# Unknown_WaterSensor.net
KiCad netlist of a schematic drawn in Altium Designer
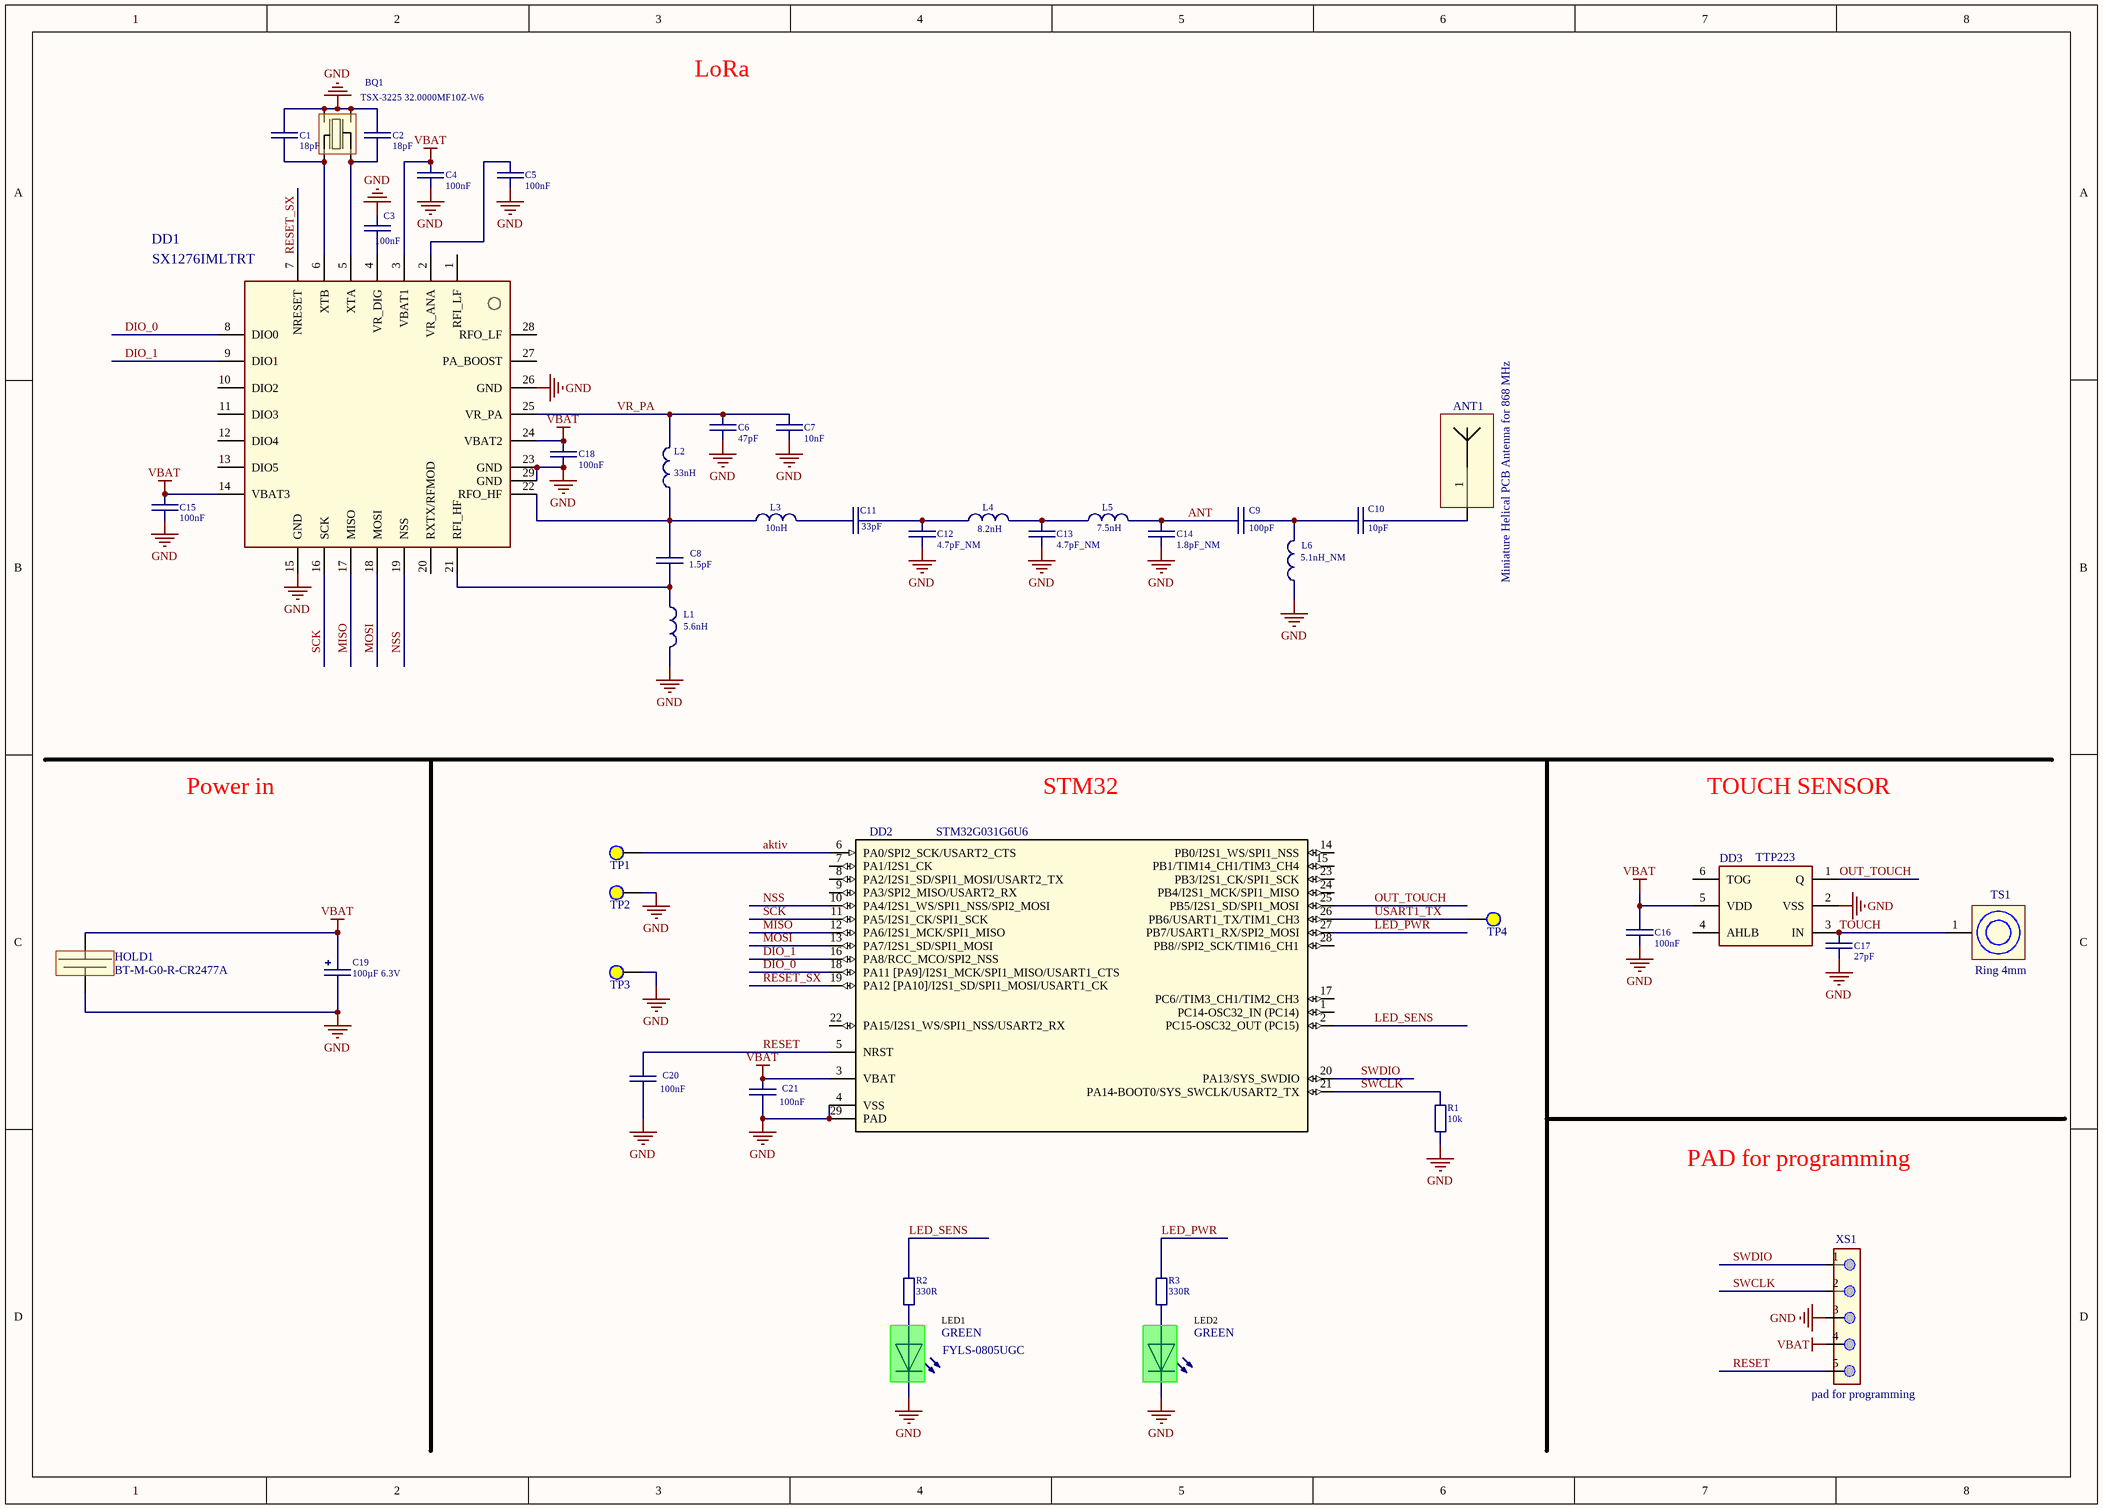
[diagram p0: Unknown WaterSensor.SCHDOC]

(export (version "E")
  (design (tool "Eeschema 10.0.6"))
  (components
    (comp (ref "ANT1")
      (value "Miniature Helical PCB Antenna for 868 MHz")
      (footprint "ANTENNA868_915MHZ_A2N")
      (libsource (lib "*") (part "Miniature Helical PCB Antenna for 868 MHz"))
    )
    (comp (ref "BQ1")
      (value "TSX-3225 32.0000MF10Z-W6")
      (footprint "3225")
      (description "32MHz ±10ppm Crystal 12pF 40 Ohms 4-SMD (3.20mm x 2.50mm)")
      (libsource (lib "CRYSTALS") (part "TSX-3225 32.0000MF10Z-W6"))
    )
    (comp (ref "C1")
      (value "C0402, 18pF, C0G")
      (footprint "C0402")
      (fields (field (name "CAPACITANCE") "18pF"))
      (libsource (lib "CAPACITORS") (part "C0402, 18pF, C0G"))
    )
    (comp (ref "C2")
      (value "C0402, 18pF, C0G")
      (footprint "C0402")
      (fields (field (name "CAPACITANCE") "18pF"))
      (libsource (lib "CAPACITORS") (part "C0402, 18pF, C0G"))
    )
    (comp (ref "C3")
      (value "C0402, 100nF,  16V, X7R")
      (footprint "C0402")
      (fields
        (field (name "MANUFACTURER") "MURATA")
        (field (name "MANUFACTURER PART NUMBER") "GRM155R71C104KA88D")
        (field (name "CAPACITANCE") "100nF")
      )
      (libsource (lib "CAPACITORS") (part "C0402, 100nF,  16V, X7R"))
    )
    (comp (ref "C4")
      (value "C0402, 100nF,  16V, X7R")
      (footprint "C0402")
      (fields
        (field (name "MANUFACTURER") "MURATA")
        (field (name "MANUFACTURER PART NUMBER") "GRM155R71C104KA88D")
        (field (name "CAPACITANCE") "100nF")
      )
      (libsource (lib "CAPACITORS") (part "C0402, 100nF,  16V, X7R"))
    )
    (comp (ref "C5")
      (value "C0402, 100nF,  16V, X7R")
      (footprint "C0402")
      (fields
        (field (name "MANUFACTURER") "MURATA")
        (field (name "MANUFACTURER PART NUMBER") "GRM155R71C104KA88D")
        (field (name "CAPACITANCE") "100nF")
      )
      (libsource (lib "CAPACITORS") (part "C0402, 100nF,  16V, X7R"))
    )
    (comp (ref "C6")
      (value "C0402, 47pF, C0G")
      (footprint "C0402")
      (fields (field (name "CAPACITANCE") "47pF"))
      (libsource (lib "*") (part "C0402, 47pF, C0G"))
    )
    (comp (ref "C7")
      (value "C0402, 10nF, X7R")
      (footprint "C0402")
      (fields (field (name "CAPACITANCE") "10nF"))
      (libsource (lib "*") (part "C0402, 10nF, X7R"))
    )
    (comp (ref "C8")
      (value "C0402, 1.5pF, C0G")
      (footprint "C0402")
      (fields (field (name "CAPACITANCE") "1.5pF"))
      (libsource (lib "CAPACITORS") (part "C0402, 1.5pF, C0G"))
    )
    (comp (ref "C9")
      (value "C0402, 100pF,  50V")
      (footprint "C0402")
      (fields (field (name "CAPACITANCE") "100pF"))
      (libsource (lib "CAPACITORS") (part "C0402, 100pF,  50V"))
    )
    (comp (ref "C10")
      (value "C0402, 10pF,  50V")
      (footprint "C0402")
      (fields (field (name "CAPACITANCE") "10pF"))
      (libsource (lib "CAPACITORS") (part "C0402, 10pF,  50V"))
    )
    (comp (ref "C11")
      (value "C0402, 33pF, C0G")
      (footprint "C0402")
      (fields (field (name "CAPACITANCE") "33pF"))
      (libsource (lib "*") (part "C0402, 33pF, C0G"))
    )
    (comp (ref "C12")
      (value "C0402, 4.7pF, C0G_NOT_MOUNT")
      (footprint "C0402")
      (fields (field (name "CAPACITANCE") "4.7pF_NM"))
      (libsource (lib "*") (part "C0402, 4.7pF, C0G"))
    )
    (comp (ref "C13")
      (value "C0402, 4.7pF, C0G_NOT_MOUNT")
      (footprint "C0402")
      (fields (field (name "CAPACITANCE") "4.7pF_NM"))
      (libsource (lib "*") (part "C0402, 4.7pF, C0G"))
    )
    (comp (ref "C14")
      (value "C0402, 1.8pF, C0G_NOT_MOUNT")
      (footprint "C0402")
      (fields (field (name "CAPACITANCE") "1.8pF_NM"))
      (libsource (lib "*") (part "C0402, 1.8pF, C0G"))
    )
    (comp (ref "C15")
      (value "C0402, 100nF,  16V, X7R")
      (footprint "C0402")
      (fields
        (field (name "MANUFACTURER") "MURATA")
        (field (name "MANUFACTURER PART NUMBER") "GRM155R71C104KA88D")
        (field (name "CAPACITANCE") "100nF")
      )
      (libsource (lib "CAPACITORS") (part "C0402, 100nF,  16V, X7R"))
    )
    (comp (ref "C16")
      (value "C0402, 100nF,  16V, X7R")
      (footprint "C0402")
      (fields
        (field (name "MANUFACTURER") "MURATA")
        (field (name "MANUFACTURER PART NUMBER") "GRM155R71C104KA88D")
        (field (name "CAPACITANCE") "100nF")
      )
      (libsource (lib "CAPACITORS") (part "C0402, 100nF,  16V, X7R"))
    )
    (comp (ref "C17")
      (value "C0402, 27pF, C0G")
      (footprint "C0402")
      (fields (field (name "CAPACITANCE") "27pF"))
      (libsource (lib "CAPACITORS") (part "C0402, 27pF, C0G"))
    )
    (comp (ref "C18")
      (value "C0402, 100nF,  16V, X7R")
      (footprint "C0402")
      (fields
        (field (name "MANUFACTURER") "MURATA")
        (field (name "MANUFACTURER PART NUMBER") "GRM155R71C104KA88D")
        (field (name "CAPACITANCE") "100nF")
      )
      (libsource (lib "CAPACITORS") (part "C0402, 100nF,  16V, X7R"))
    )
    (comp (ref "C19")
      (value "865080142007")
      (footprint "WCAP-ASLI_5x5.5")
      (description "Aluminium Electrolytic Capacitors - SMD WCAP-ASLI 100uF 6.3V 20% SMD/SMT")
      (fields (field (name "ALTIUM_UNNAMED_1") "100µF 6.3V"))
      (libsource (lib "*") (part "865080142007"))
    )
    (comp (ref "C20")
      (value "C0402, 100nF,  16V, X7R")
      (footprint "C0402")
      (fields
        (field (name "MANUFACTURER") "MURATA")
        (field (name "MANUFACTURER PART NUMBER") "GRM155R71C104KA88D")
        (field (name "CAPACITANCE") "100nF")
      )
      (libsource (lib "CAPACITORS") (part "C0402, 100nF,  16V, X7R"))
    )
    (comp (ref "C21")
      (value "C0402, 100nF,  16V, X7R")
      (footprint "C0402")
      (fields
        (field (name "MANUFACTURER") "MURATA")
        (field (name "MANUFACTURER PART NUMBER") "GRM155R71C104KA88D")
        (field (name "CAPACITANCE") "100nF")
      )
      (libsource (lib "CAPACITORS") (part "C0402, 100nF,  16V, X7R"))
    )
    (comp (ref "DD1")
      (value "SX1276IMLTRT")
      (footprint "vqfn28_6x6mm")
      (description "SX1276 - Low Power Integrated UHF Transceiver with loRa Modem")
      (libsource (lib "DIGITAL and ANALOG ICs") (part "SX1276IMLTRT"))
    )
    (comp (ref "DD2")
      (value "STM32G031G6U6")
      (footprint "UFQFPN-28")
      (description "ARM® Cortex®-M0+ STM32G0 Microcontroller IC 32-Bit 64MHz 32KB (32K x 8) FLASH 28-UFQFPN (4x4)")
      (libsource (lib "SparkFun") (part "STM32G031G6U6"))
    )
    (comp (ref "DD3")
      (value "TTP223")
      (footprint "SOT23-6")
      (description "1 KEY TOUCH PAD DETECTOR IC")
      (libsource (lib "DIGITAL and ANALOG ICs") (part "TTP223"))
    )
    (comp (ref "HOLD1")
      (value "BT-M-G0-R-CR2477A")
      (footprint "SMTU2477N-LF")
      (description "Coin Cell Battery Holders FOR CR2477N, SMD")
      (libsource (lib "CONNECTORS") (part "SMTU2477N-LF"))
    )
    (comp (ref "L1")
      (value "LQG15HS5N6C02D")
      (footprint "L0402")
      (description "L0402, 5.6nH")
      (fields (field (name "ALTIUM_UNNAMED_1") "5.6nH"))
      (libsource (lib "INDUCTORS") (part "LQG15HS5N6C02D"))
    )
    (comp (ref "L2")
      (value "LQW15AN33NJ00D")
      (footprint "L0402")
      (description "L0402, 33nH")
      (fields (field (name "ALTIUM_UNNAMED_1") "33nH"))
      (libsource (lib "INDUCTORS") (part "LQW15AN33NJ00D"))
    )
    (comp (ref "L3")
      (value "LQG15HS10NJ02D")
      (footprint "L0402")
      (description "L0402, 10nH")
      (fields (field (name "ALTIUM_UNNAMED_1") "10nH"))
      (libsource (lib "*") (part "LQG15HS10NJ02D"))
    )
    (comp (ref "L4")
      (value "LQG15HS8N2J02D")
      (footprint "L0402")
      (description "L0402, 8.2nH")
      (fields (field (name "ALTIUM_UNNAMED_1") "8.2nH"))
      (libsource (lib "*") (part "LQG15HS8N2J02D"))
    )
    (comp (ref "L5")
      (value "LQG15HS7N5J02D")
      (footprint "L0402")
      (description "L0402, 7.5nH")
      (fields (field (name "ALTIUM_UNNAMED_1") "7.5nH"))
      (libsource (lib "*") (part "LQG15HS7N5J02D"))
    )
    (comp (ref "L6")
      (value "LQG15HN5N1S02D_NOT_MOUNT")
      (footprint "L0402")
      (description "L0402, 5.1nH_NOT_MOUNT")
      (fields (field (name "ALTIUM_UNNAMED_1") "5.1nH_NM"))
      (libsource (lib "*") (part "LQG15HN5N1S02D"))
    )
    (comp (ref "LED1")
      (value "FYLS-0805UGC")
      (footprint "LED_0805_G")
      (description "LED, GREEN, 0805")
      (fields (field (name "ALTIUM_UNNAMED_1") "GREEN"))
      (libsource (lib "LED") (part "FYLS-0805UGC"))
    )
    (comp (ref "LED2")
      (value "FYLS-0805UGC")
      (footprint "LED_0805_G")
      (description "LED, GREEN, 0805")
      (fields (field (name "ALTIUM_UNNAMED_1") "GREEN"))
      (libsource (lib "LED") (part "FYLS-0805UGC"))
    )
    (comp (ref "R1")
      (value "R0402, 10k 1%")
      (footprint "R0402")
      (fields (field (name "PART NUMBER") "RC0402JR-0710KL_YAGEO") (field (name "RESISTANCE") "10k"))
      (libsource (lib "RESISTOR") (part "R0402, 10k 1%"))
    )
    (comp (ref "R2")
      (value "R0402, 330R 5%")
      (footprint "R0402")
      (fields
        (field (name "RESISTANCE") "330R")
        (field (name "MANUFACTURER") "Panasonic Electronic Components")
        (field (name "TOLERANCE") "5 %")
        (field (name "MANUFACTURER PART NUMBER") "ERJ-2GEJ331X")
      )
      (libsource (lib "RESISTOR") (part "R0402, 330R 5%"))
    )
    (comp (ref "R3")
      (value "R0402, 330R 5%")
      (footprint "R0402")
      (fields
        (field (name "RESISTANCE") "330R")
        (field (name "MANUFACTURER") "Panasonic Electronic Components")
        (field (name "TOLERANCE") "5 %")
        (field (name "MANUFACTURER PART NUMBER") "ERJ-2GEJ331X")
      )
      (libsource (lib "RESISTOR") (part "R0402, 330R 5%"))
    )
    (comp (ref "TP1")
      (value "Test Point 1mm pad")
      (footprint "Test Point 1mm")
      (libsource (lib "CONNECTORS") (part "Test Point 1mm pad"))
    )
    (comp (ref "TP2")
      (value "Test Point 1mm pad")
      (footprint "Test Point 1mm")
      (libsource (lib "CONNECTORS") (part "Test Point 1mm pad"))
    )
    (comp (ref "TP3")
      (value "Test Point 1mm pad")
      (footprint "Test Point 1mm")
      (libsource (lib "CONNECTORS") (part "Test Point 1mm pad"))
    )
    (comp (ref "TP4")
      (value "Test Point 1mm pad")
      (footprint "Test Point 1mm")
      (libsource (lib "CONNECTORS") (part "Test Point 1mm pad"))
    )
    (comp (ref "TS1")
      (value "Ring 4mm")
      (footprint "Ring 4mm")
      (description "touch spring 13x8.5mm")
      (libsource (lib "*") (part "Ring 4mm"))
    )
    (comp (ref "XS1")
      (value "pad for programming")
      (footprint "pad for programming 5x2mm")
      (description "pad for programming 5x2mm")
      (libsource (lib "*") (part "pad for programming 5x2mm"))
    )
  )
  (nets
    (net (code "1") (name "/ANT") (class "Default")
      (node (ref "C14") (pin "2") (pintype "passive"))
      (node (ref "C9") (pin "1") (pintype "passive"))
      (node (ref "L5") (pin "2") (pinfunction "2_2") (pintype "passive"))
    )
    (net (code "2") (name "/DIO_0") (class "Default")
      (node (ref "DD1") (pin "8") (pinfunction "DIO0_8") (pintype "passive"))
      (node (ref "DD2") (pin "18") (pinfunction "PA11_[PA9]/I2S1_MCK/SPI1_MISO/USART1_CTS_18") (pintype "bidirectional"))
    )
    (net (code "3") (name "/DIO_1") (class "Default")
      (node (ref "DD1") (pin "9") (pinfunction "DIO1_9") (pintype "passive"))
      (node (ref "DD2") (pin "16") (pinfunction "PA8/RCC_MCO/SPI2_NSS_16") (pintype "bidirectional"))
    )
    (net (code "4") (name "/LED_PWR") (class "Default")
      (node (ref "DD2") (pin "27") (pinfunction "PB7/USART1_RX/SPI2_MOSI_27") (pintype "bidirectional"))
      (node (ref "R3") (pin "2") (pintype "passive"))
    )
    (net (code "5") (name "/LED_SENS") (class "Default")
      (node (ref "DD2") (pin "2") (pinfunction "PC15-OSC32_OUT_(PC15)_2") (pintype "bidirectional"))
      (node (ref "R2") (pin "2") (pintype "passive"))
    )
    (net (code "6") (name "/MISO") (class "Default")
      (node (ref "DD1") (pin "17") (pinfunction "MISO_17") (pintype "passive"))
      (node (ref "DD2") (pin "12") (pinfunction "PA6/I2S1_MCK/SPI1_MISO_12") (pintype "bidirectional"))
    )
    (net (code "7") (name "/MOSI") (class "Default")
      (node (ref "DD1") (pin "18") (pinfunction "MOSI_18") (pintype "passive"))
      (node (ref "DD2") (pin "13") (pinfunction "PA7/I2S1_SD/SPI1_MOSI_13") (pintype "bidirectional"))
    )
    (net (code "8") (name "/NSS") (class "Default")
      (node (ref "DD1") (pin "19") (pinfunction "NSS_19") (pintype "passive"))
      (node (ref "DD2") (pin "10") (pinfunction "PA4/I2S1_WS/SPI1_NSS/SPI2_MOSI_10") (pintype "bidirectional"))
    )
    (net (code "9") (name "/OUT_TOUCH") (class "Default")
      (node (ref "DD2") (pin "25") (pinfunction "PB5/I2S1_SD/SPI1_MOSI_25") (pintype "bidirectional"))
      (node (ref "DD3") (pin "1") (pinfunction "Q_1") (pintype "passive"))
    )
    (net (code "10") (name "/RESET") (class "Default")
      (node (ref "C20") (pin "1") (pintype "passive"))
      (node (ref "DD2") (pin "5") (pinfunction "NRST_5") (pintype "power_in"))
      (node (ref "XS1") (pin "5") (pinfunction "5_5") (pintype "passive"))
    )
    (net (code "11") (name "/RESET_SX") (class "Default")
      (node (ref "DD1") (pin "7") (pinfunction "NRESET_7") (pintype "passive"))
      (node (ref "DD2") (pin "19") (pinfunction "PA12_[PA10]/I2S1_SD/SPI1_MOSI/USART1_CK_19") (pintype "bidirectional"))
    )
    (net (code "12") (name "/SCK") (class "Default")
      (node (ref "DD1") (pin "16") (pinfunction "SCK_16") (pintype "passive"))
      (node (ref "DD2") (pin "11") (pinfunction "PA5/I2S1_CK/SPI1_SCK_11") (pintype "bidirectional"))
    )
    (net (code "13") (name "/SWCLK") (class "Default")
      (node (ref "DD2") (pin "21") (pinfunction "PA14-BOOT0/SYS_SWCLK/USART2_TX_21") (pintype "bidirectional"))
      (node (ref "R1") (pin "1") (pintype "passive"))
      (node (ref "XS1") (pin "2") (pinfunction "2_2") (pintype "passive"))
    )
    (net (code "14") (name "/SWDIO") (class "Default")
      (node (ref "DD2") (pin "20") (pinfunction "PA13/SYS_SWDIO_20") (pintype "bidirectional"))
      (node (ref "XS1") (pin "1") (pinfunction "1_1") (pintype "passive"))
    )
    (net (code "15") (name "/TOUCH") (class "Default")
      (node (ref "C17") (pin "2") (pintype "passive"))
      (node (ref "DD3") (pin "3") (pinfunction "IN_3") (pintype "passive"))
      (node (ref "TS1") (pin "1") (pinfunction "1_1") (pintype "passive"))
    )
    (net (code "16") (name "/USART1_TX") (class "Default")
      (node (ref "DD2") (pin "26") (pinfunction "PB6/USART1_TX/TIM1_CH3_26") (pintype "bidirectional"))
      (node (ref "TP4") (pin "1") (pinfunction "1_1") (pintype "passive"))
    )
    (net (code "17") (name "/VR_PA") (class "Default")
      (node (ref "C6") (pin "2") (pintype "passive"))
      (node (ref "C7") (pin "2") (pintype "passive"))
      (node (ref "DD1") (pin "25") (pinfunction "VR_PA_25") (pintype "passive"))
      (node (ref "L2") (pin "2") (pinfunction "2_2") (pintype "passive"))
    )
    (net (code "18") (name "/aktiv") (class "Default")
      (node (ref "DD2") (pin "6") (pinfunction "PA0/SPI2_SCK/USART2_CTS_6") (pintype "input"))
      (node (ref "TP1") (pin "1") (pinfunction "1_1") (pintype "passive"))
    )
    (net (code "19") (name "GND") (class "Default")
      (node (ref "BQ1") (pin "2") (pinfunction "GND_2") (pintype "power_in"))
      (node (ref "BQ1") (pin "4") (pinfunction "GND_4") (pintype "power_in"))
      (node (ref "C1") (pin "2") (pintype "passive"))
      (node (ref "C12") (pin "1") (pintype "passive"))
      (node (ref "C13") (pin "1") (pintype "passive"))
      (node (ref "C14") (pin "1") (pintype "passive"))
      (node (ref "C15") (pin "2") (pintype "passive"))
      (node (ref "C16") (pin "2") (pintype "passive"))
      (node (ref "C17") (pin "1") (pintype "passive"))
      (node (ref "C18") (pin "2") (pintype "passive"))
      (node (ref "C19") (pin "1") (pintype "passive"))
      (node (ref "C2") (pin "2") (pintype "passive"))
      (node (ref "C20") (pin "2") (pintype "passive"))
      (node (ref "C21") (pin "2") (pintype "passive"))
      (node (ref "C3") (pin "1") (pintype "passive"))
      (node (ref "C4") (pin "2") (pintype "passive"))
      (node (ref "C5") (pin "2") (pintype "passive"))
      (node (ref "C6") (pin "1") (pintype "passive"))
      (node (ref "C7") (pin "1") (pintype "passive"))
      (node (ref "DD1") (pin "15") (pinfunction "GND_15") (pintype "passive"))
      (node (ref "DD1") (pin "23") (pinfunction "GND_23") (pintype "passive"))
      (node (ref "DD1") (pin "26") (pinfunction "GND_26") (pintype "passive"))
      (node (ref "DD1") (pin "29") (pinfunction "GND_29") (pintype "passive"))
      (node (ref "DD2") (pin "29") (pinfunction "PAD_29") (pintype "passive"))
      (node (ref "DD2") (pin "4") (pinfunction "VSS_4") (pintype "power_in"))
      (node (ref "DD3") (pin "2") (pinfunction "VSS_2") (pintype "passive"))
      (node (ref "HOLD1") (pin "2") (pinfunction "2_2") (pintype "passive"))
      (node (ref "L1") (pin "2") (pinfunction "2_2") (pintype "passive"))
      (node (ref "L6") (pin "1") (pinfunction "1_1") (pintype "passive"))
      (node (ref "LED1") (pin "1") (pinfunction "K_1") (pintype "passive"))
      (node (ref "LED2") (pin "1") (pinfunction "K_1") (pintype "passive"))
      (node (ref "R1") (pin "2") (pintype "passive"))
      (node (ref "TP2") (pin "1") (pinfunction "1_1") (pintype "passive"))
      (node (ref "TP3") (pin "1") (pinfunction "1_1") (pintype "passive"))
      (node (ref "XS1") (pin "3") (pinfunction "3_3") (pintype "passive"))
    )
    (net (code "20") (name "Net-(ANT1-Pad1)") (class "Default")
      (node (ref "ANT1") (pin "1") (pinfunction "1_1") (pintype "passive"))
      (node (ref "C10") (pin "2") (pintype "passive"))
    )
    (net (code "21") (name "Net-(C10-Pad1)") (class "Default")
      (node (ref "C10") (pin "1") (pintype "passive"))
      (node (ref "C9") (pin "2") (pintype "passive"))
      (node (ref "L6") (pin "2") (pinfunction "2_2") (pintype "passive"))
    )
    (net (code "22") (name "Net-(C11-Pad1)") (class "Default")
      (node (ref "C11") (pin "1") (pintype "passive"))
      (node (ref "L3") (pin "2") (pinfunction "2_2") (pintype "passive"))
    )
    (net (code "23") (name "Net-(C11-Pad2)") (class "Default")
      (node (ref "C11") (pin "2") (pintype "passive"))
      (node (ref "C12") (pin "2") (pintype "passive"))
      (node (ref "L4") (pin "1") (pinfunction "1_1") (pintype "passive"))
    )
    (net (code "24") (name "Net-(C13-Pad2)") (class "Default")
      (node (ref "C13") (pin "2") (pintype "passive"))
      (node (ref "L4") (pin "2") (pinfunction "2_2") (pintype "passive"))
      (node (ref "L5") (pin "1") (pinfunction "1_1") (pintype "passive"))
    )
    (net (code "25") (name "Net-(DD1-RFI_HF)") (class "Default")
      (node (ref "C8") (pin "1") (pintype "passive"))
      (node (ref "DD1") (pin "21") (pinfunction "RFI_HF_21") (pintype "passive"))
      (node (ref "L1") (pin "1") (pinfunction "1_1") (pintype "passive"))
    )
    (net (code "26") (name "Net-(DD1-RFO_HF)") (class "Default")
      (node (ref "C8") (pin "2") (pintype "passive"))
      (node (ref "DD1") (pin "22") (pinfunction "RFO_HF_22") (pintype "passive"))
      (node (ref "L2") (pin "1") (pinfunction "1_1") (pintype "passive"))
      (node (ref "L3") (pin "1") (pinfunction "1_1") (pintype "passive"))
    )
    (net (code "27") (name "Net-(DD1-VR_ANA)") (class "Default")
      (node (ref "C5") (pin "1") (pintype "passive"))
      (node (ref "DD1") (pin "2") (pinfunction "VR_ANA_2") (pintype "passive"))
    )
    (net (code "28") (name "Net-(DD1-VR_DIG)") (class "Default")
      (node (ref "C3") (pin "2") (pintype "passive"))
      (node (ref "DD1") (pin "4") (pinfunction "VR_DIG_4") (pintype "passive"))
    )
    (net (code "29") (name "Net-(DD1-XTA)") (class "Default")
      (node (ref "BQ1") (pin "1") (pinfunction "1_1") (pintype "passive"))
      (node (ref "C2") (pin "1") (pintype "passive"))
      (node (ref "DD1") (pin "5") (pinfunction "XTA_5") (pintype "passive"))
    )
    (net (code "30") (name "Net-(DD1-XTB)") (class "Default")
      (node (ref "BQ1") (pin "3") (pinfunction "3_3") (pintype "passive"))
      (node (ref "C1") (pin "1") (pintype "passive"))
      (node (ref "DD1") (pin "6") (pinfunction "XTB_6") (pintype "passive"))
    )
    (net (code "31") (name "Net-(LED1-A)") (class "Default")
      (node (ref "LED1") (pin "2") (pinfunction "A_2") (pintype "passive"))
      (node (ref "R2") (pin "1") (pintype "passive"))
    )
    (net (code "32") (name "Net-(LED2-A)") (class "Default")
      (node (ref "LED2") (pin "2") (pinfunction "A_2") (pintype "passive"))
      (node (ref "R3") (pin "1") (pintype "passive"))
    )
    (net (code "33") (name "VBAT") (class "Default")
      (node (ref "C15") (pin "1") (pintype "passive"))
      (node (ref "C16") (pin "1") (pintype "passive"))
      (node (ref "C18") (pin "1") (pintype "passive"))
      (node (ref "C19") (pin "2") (pintype "passive"))
      (node (ref "C21") (pin "1") (pintype "passive"))
      (node (ref "C4") (pin "1") (pintype "passive"))
      (node (ref "DD1") (pin "14") (pinfunction "VBAT3_14") (pintype "passive"))
      (node (ref "DD1") (pin "24") (pinfunction "VBAT2_24") (pintype "passive"))
      (node (ref "DD1") (pin "3") (pinfunction "VBAT1_3") (pintype "passive"))
      (node (ref "DD2") (pin "3") (pinfunction "VBAT_3") (pintype "passive"))
      (node (ref "DD3") (pin "5") (pinfunction "VDD_5") (pintype "passive"))
      (node (ref "HOLD1") (pin "1") (pinfunction "1_1") (pintype "passive"))
      (node (ref "XS1") (pin "4") (pinfunction "4_4") (pintype "passive"))
    )
    (net (code "34") (name "unconnected-(DD1-DIO2-Pad10)") (class "Default")
      (node (ref "DD1") (pin "10") (pinfunction "DIO2_10") (pintype "passive"))
    )
    (net (code "35") (name "unconnected-(DD1-DIO3-Pad11)") (class "Default")
      (node (ref "DD1") (pin "11") (pinfunction "DIO3_11") (pintype "passive"))
    )
    (net (code "36") (name "unconnected-(DD1-DIO4-Pad12)") (class "Default")
      (node (ref "DD1") (pin "12") (pinfunction "DIO4_12") (pintype "passive"))
    )
    (net (code "37") (name "unconnected-(DD1-DIO5-Pad13)") (class "Default")
      (node (ref "DD1") (pin "13") (pinfunction "DIO5_13") (pintype "passive"))
    )
    (net (code "38") (name "unconnected-(DD1-PA_BOOST-Pad27)") (class "Default")
      (node (ref "DD1") (pin "27") (pinfunction "PA_BOOST_27") (pintype "passive"))
    )
    (net (code "39") (name "unconnected-(DD1-RFI_LF-Pad1)") (class "Default")
      (node (ref "DD1") (pin "1") (pinfunction "RFI_LF_1") (pintype "passive"))
    )
    (net (code "40") (name "unconnected-(DD1-RFO_LF-Pad28)") (class "Default")
      (node (ref "DD1") (pin "28") (pinfunction "RFO_LF_28") (pintype "passive"))
    )
    (net (code "41") (name "unconnected-(DD1-RXTX{slash}RFMOD-Pad20)") (class "Default")
      (node (ref "DD1") (pin "20") (pinfunction "RXTX/RFMOD_20") (pintype "passive"))
    )
    (net (code "42") (name "unconnected-(DD2-PA1{slash}I2S1_CK-Pad7)") (class "Default")
      (node (ref "DD2") (pin "7") (pinfunction "PA1/I2S1_CK_7") (pintype "bidirectional"))
    )
    (net (code "43") (name "unconnected-(DD2-PA2{slash}I2S1_SD{slash}SPI1_MOSI{slash}USART2_TX-Pad8)") (class "Default")
      (node (ref "DD2") (pin "8") (pinfunction "PA2/I2S1_SD/SPI1_MOSI/USART2_TX_8") (pintype "bidirectional"))
    )
    (net (code "44") (name "unconnected-(DD2-PA3{slash}SPI2_MISO{slash}USART2_RX-Pad9)") (class "Default")
      (node (ref "DD2") (pin "9") (pinfunction "PA3/SPI2_MISO/USART2_RX_9") (pintype "bidirectional"))
    )
    (net (code "45") (name "unconnected-(DD2-PA15{slash}I2S1_WS{slash}SPI1_NSS{slash}USART2_RX-Pad22)") (class "Default")
      (node (ref "DD2") (pin "22") (pinfunction "PA15/I2S1_WS/SPI1_NSS/USART2_RX_22") (pintype "bidirectional"))
    )
    (net (code "46") (name "unconnected-(DD2-PB0{slash}I2S1_WS{slash}SPI1_NSS-Pad14)") (class "Default")
      (node (ref "DD2") (pin "14") (pinfunction "PB0/I2S1_WS/SPI1_NSS_14") (pintype "bidirectional"))
    )
    (net (code "47") (name "unconnected-(DD2-PB1{slash}TIM14_CH1{slash}TIM3_CH4-Pad15)") (class "Default")
      (node (ref "DD2") (pin "15") (pinfunction "PB1/TIM14_CH1/TIM3_CH4_15") (pintype "bidirectional"))
    )
    (net (code "48") (name "unconnected-(DD2-PB3{slash}I2S1_CK{slash}SPI1_SCK-Pad23)") (class "Default")
      (node (ref "DD2") (pin "23") (pinfunction "PB3/I2S1_CK/SPI1_SCK_23") (pintype "bidirectional"))
    )
    (net (code "49") (name "unconnected-(DD2-PB4{slash}I2S1_MCK{slash}SPI1_MISO-Pad24)") (class "Default")
      (node (ref "DD2") (pin "24") (pinfunction "PB4/I2S1_MCK/SPI1_MISO_24") (pintype "bidirectional"))
    )
    (net (code "50") (name "unconnected-(DD2-PB8{slash}{slash}SPI2_SCK{slash}TIM16_CH1-Pad28)") (class "Default")
      (node (ref "DD2") (pin "28") (pinfunction "PB8//SPI2_SCK/TIM16_CH1_28") (pintype "bidirectional"))
    )
    (net (code "51") (name "unconnected-(DD2-PC6{slash}{slash}TIM3_CH1{slash}TIM2_CH3-Pad17)") (class "Default")
      (node (ref "DD2") (pin "17") (pinfunction "PC6//TIM3_CH1/TIM2_CH3_17") (pintype "bidirectional"))
    )
    (net (code "52") (name "unconnected-(DD2-PC14-OSC32_IN_(PC14)-Pad1)") (class "Default")
      (node (ref "DD2") (pin "1") (pinfunction "PC14-OSC32_IN_(PC14)_1") (pintype "bidirectional"))
    )
    (net (code "53") (name "unconnected-(DD3-AHLB-Pad4)") (class "Default")
      (node (ref "DD3") (pin "4") (pinfunction "AHLB_4") (pintype "passive"))
    )
    (net (code "54") (name "unconnected-(DD3-TOG-Pad6)") (class "Default")
      (node (ref "DD3") (pin "6") (pinfunction "TOG_6") (pintype "passive"))
    )
  )
)
